# PWR_DC_IN.net
KiCad netlist of a schematic drawn in Altium Designer
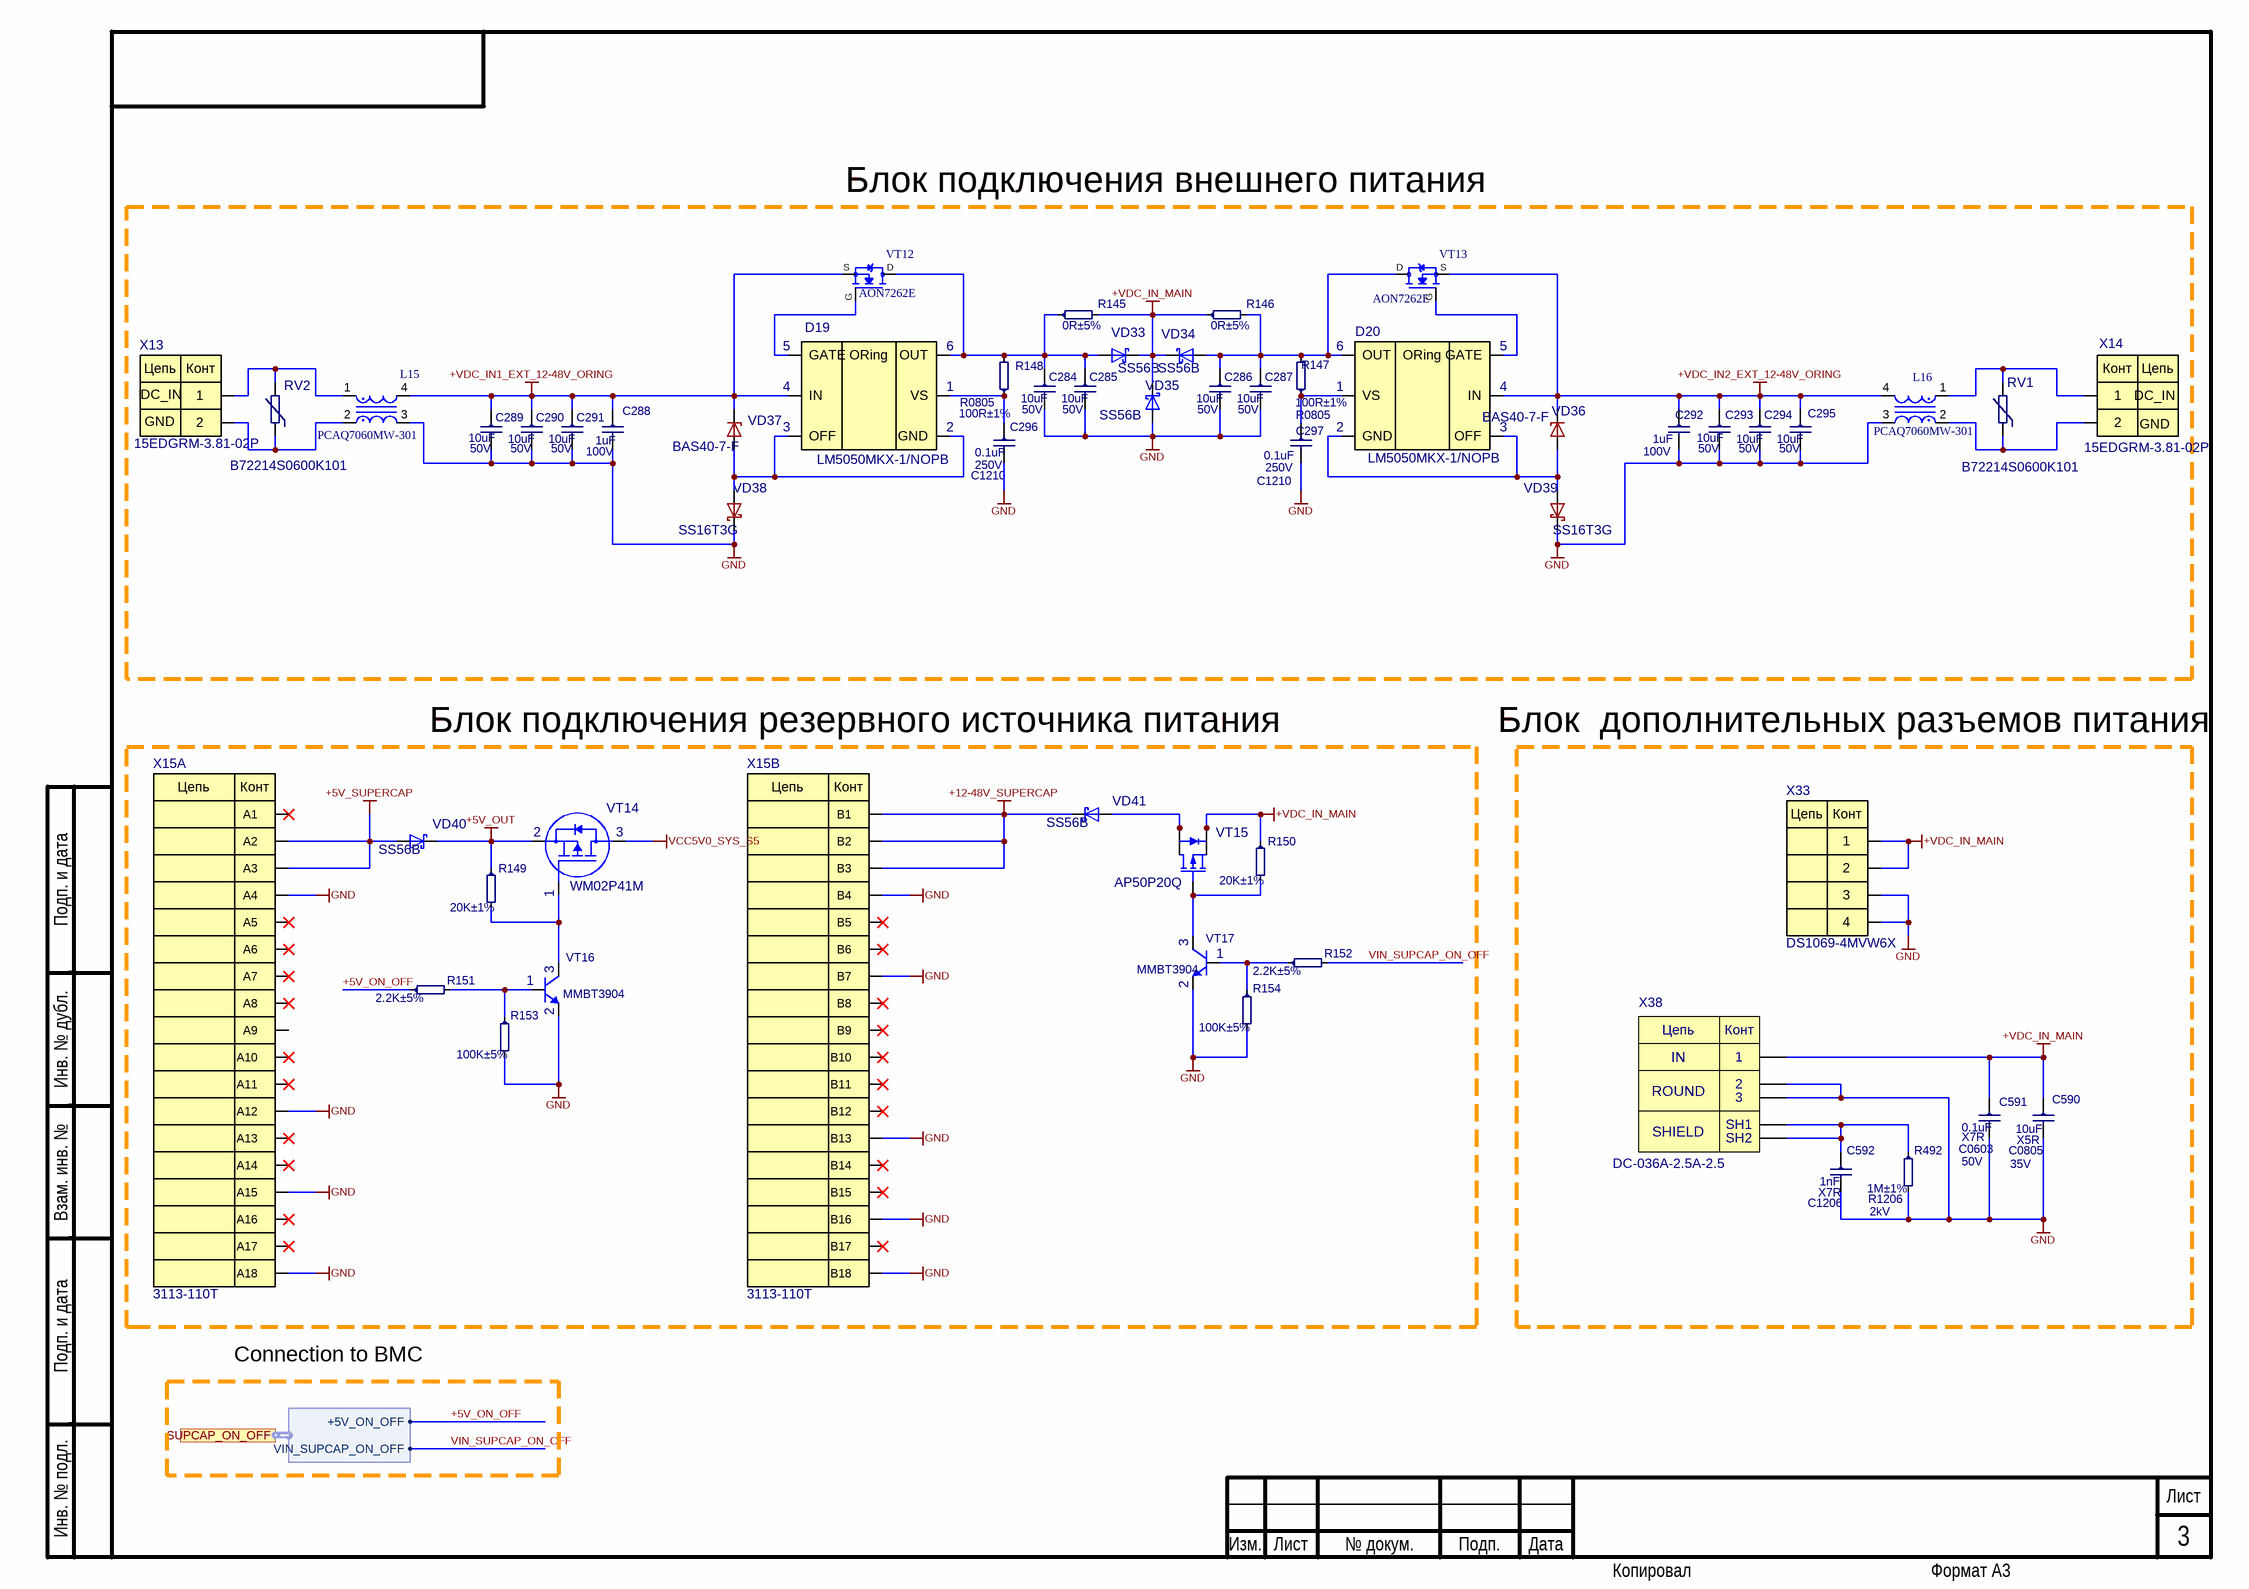
[diagram p0: PWR_DC_IN.SchDoc]

(export (version "E")
  (design (tool "Eeschema 10.0.6"))
  (components
    (comp (ref "C284")
      (value "10uF")
      (footprint "C1206")
      (fields
        (field (name "VOLTAGE") "50V")
        (field (name "PART NUMBER") "1206-X5R-50V-010uF±10%")
        (field (name "TOLERANCE") "10%")
        (field (name "MANUFACTURER") "Yageo")
      )
      (libsource (lib "ATB") (part "C"))
    )
    (comp (ref "C285")
      (value "10uF")
      (footprint "C1206")
      (fields
        (field (name "VOLTAGE") "50V")
        (field (name "PART NUMBER") "1206-X5R-50V-010uF±10%")
        (field (name "TOLERANCE") "10%")
        (field (name "MANUFACTURER") "Yageo")
      )
      (libsource (lib "ATB") (part "C"))
    )
    (comp (ref "C286")
      (value "10uF")
      (footprint "C1206")
      (fields
        (field (name "VOLTAGE") "50V")
        (field (name "PART NUMBER") "1206-X5R-50V-010uF±10%")
        (field (name "TOLERANCE") "10%")
        (field (name "MANUFACTURER") "Yageo")
      )
      (libsource (lib "ATB") (part "C"))
    )
    (comp (ref "C287")
      (value "10uF")
      (footprint "C1206")
      (fields
        (field (name "VOLTAGE") "50V")
        (field (name "PART NUMBER") "1206-X5R-50V-010uF±10%")
        (field (name "TOLERANCE") "10%")
        (field (name "MANUFACTURER") "Yageo")
      )
      (libsource (lib "ATB") (part "C"))
    )
    (comp (ref "C288")
      (value "1uF")
      (footprint "C1206")
      (fields
        (field (name "VOLTAGE") "100V")
        (field (name "PART NUMBER") "1206-X7R-100V-1uF±10%")
        (field (name "TOLERANCE") "10%")
        (field (name "MANUFACTURER") "CCTC")
      )
      (libsource (lib "ATB") (part "C"))
    )
    (comp (ref "C289")
      (value "10uF")
      (footprint "C1206")
      (fields
        (field (name "VOLTAGE") "50V")
        (field (name "PART NUMBER") "1206-X5R-50V-010uF±10%")
        (field (name "TOLERANCE") "10%")
        (field (name "MANUFACTURER") "Yageo")
      )
      (libsource (lib "ATB") (part "C"))
    )
    (comp (ref "C290")
      (value "10uF")
      (footprint "C1206")
      (fields
        (field (name "VOLTAGE") "50V")
        (field (name "PART NUMBER") "1206-X5R-50V-010uF±10%")
        (field (name "TOLERANCE") "10%")
        (field (name "MANUFACTURER") "Yageo")
      )
      (libsource (lib "ATB") (part "C"))
    )
    (comp (ref "C291")
      (value "10uF")
      (footprint "C1206")
      (fields
        (field (name "VOLTAGE") "50V")
        (field (name "PART NUMBER") "1206-X5R-50V-010uF±10%")
        (field (name "TOLERANCE") "10%")
        (field (name "MANUFACTURER") "Yageo")
      )
      (libsource (lib "ATB") (part "C"))
    )
    (comp (ref "C292")
      (value "1uF")
      (footprint "C1206")
      (fields
        (field (name "VOLTAGE") "100V")
        (field (name "PART NUMBER") "1206-X7R-100V-1uF±10%")
        (field (name "TOLERANCE") "10%")
        (field (name "MANUFACTURER") "CCTC")
      )
      (libsource (lib "ATB") (part "C"))
    )
    (comp (ref "C293")
      (value "10uF")
      (footprint "C1206")
      (fields
        (field (name "VOLTAGE") "50V")
        (field (name "PART NUMBER") "1206-X5R-50V-010uF±10%")
        (field (name "TOLERANCE") "10%")
        (field (name "MANUFACTURER") "Yageo")
      )
      (libsource (lib "ATB") (part "C"))
    )
    (comp (ref "C294")
      (value "10uF")
      (footprint "C1206")
      (fields
        (field (name "VOLTAGE") "50V")
        (field (name "PART NUMBER") "1206-X5R-50V-010uF±10%")
        (field (name "TOLERANCE") "10%")
        (field (name "MANUFACTURER") "Yageo")
      )
      (libsource (lib "ATB") (part "C"))
    )
    (comp (ref "C295")
      (value "10uF")
      (footprint "C1206")
      (fields
        (field (name "VOLTAGE") "50V")
        (field (name "PART NUMBER") "1206-X5R-50V-010uF±10%")
        (field (name "TOLERANCE") "10%")
        (field (name "MANUFACTURER") "Yageo")
      )
      (libsource (lib "ATB") (part "C"))
    )
    (comp (ref "C296")
      (value "0.1uF")
      (footprint "C1210")
      (fields
        (field (name "VOLTAGE") "250V")
        (field (name "CASE") "C1210")
        (field (name "PART NUMBER") "1210-X7R-250V-0.1uF±10%")
        (field (name "TOLERANCE") "10%")
        (field (name "MANUFACTURER") "Yageo")
      )
      (libsource (lib "ATB") (part "C"))
    )
    (comp (ref "C297")
      (value "0.1uF")
      (footprint "C1210")
      (fields
        (field (name "VOLTAGE") "250V")
        (field (name "CASE") "C1210")
        (field (name "PART NUMBER") "1210-X7R-250V-0.1uF±10%")
        (field (name "TOLERANCE") "10%")
        (field (name "MANUFACTURER") "Yageo")
      )
      (libsource (lib "ATB") (part "C"))
    )
    (comp (ref "C590")
      (value "10uF")
      (footprint "C0805")
      (fields
        (field (name "DIELECTRIC") "X5R")
        (field (name "VOLTAGE") "35V")
        (field (name "CASE") "C0805")
        (field (name "PART NUMBER") "0805-X5R-35V-10uF±10%")
        (field (name "TOLERANCE") "10%")
        (field (name "MANUFACTURER") "TDK Corporation")
      )
      (libsource (lib "ATB") (part "C"))
    )
    (comp (ref "C591")
      (value "0.1uF")
      (footprint "C0603")
      (fields
        (field (name "DIELECTRIC") "X7R")
        (field (name "VOLTAGE") "50V")
        (field (name "CASE") "C0603")
        (field (name "PART NUMBER") "0603-X7R-50V-0.1uF±10%")
        (field (name "TOLERANCE") "10%")
        (field (name "MANUFACTURER") "Yageo")
      )
      (libsource (lib "ATB") (part "C"))
    )
    (comp (ref "C592")
      (value "1nF")
      (footprint "C1206")
      (description "Ceramic Capacitor 1206 1nF ±10% 2kV X7R")
      (fields
        (field (name "DIELECTRIC") "X7R")
        (field (name "VOLTAGE") "2kV")
        (field (name "CASE") "C1206")
        (field (name "PART NUMBER") "1206-X7R-2K-1000pF±10%")
        (field (name "TOLERANCE") "10%")
      )
      (libsource (lib "ATB") (part "C"))
    )
    (comp (ref "D19")
      (value "LM5050MKX-1/NOPB")
      (footprint "LM5050MKX-1/NOPB")
      (description "High-Side OR-ing FET Controller")
      (fields (field (name "MANUFACTURER") "TI"))
      (libsource (lib "") (part "LM5050MKX-1/NOPB_1"))
    )
    (comp (ref "D20")
      (value "LM5050MKX-1/NOPB")
      (footprint "LM5050MKX-1/NOPB")
      (description "High-Side OR-ing FET Controller")
      (fields (field (name "MANUFACTURER") "TI"))
      (libsource (lib "LIB_RK") (part "LM5050MKX-1/NOPB"))
    )
    (comp (ref "L15")
      (value "PCAQ7060MW-301")
      (footprint "PCAQ7060MW-301")
      (description "300Ω@100MHz 10mΩ 2 SMD,7x6x3.8mm")
      (fields (field (name "MF") "Panasonic Electronic") (field (name "MP") "EEH-ZA1V151P"))
      (libsource (lib "") (part "PCAQ7060MW-301_1"))
    )
    (comp (ref "L16")
      (value "PCAQ7060MW-301")
      (footprint "PCAQ7060MW-301")
      (description "300Ω@100MHz 10mΩ 2 SMD,7x6x3.8mm")
      (fields (field (name "MF") "Panasonic Electronic") (field (name "MP") "EEH-ZA1V151P"))
      (libsource (lib "LIB_RK") (part "PCAQ7060MW-301"))
    )
    (comp (ref "R145")
      (value "0R±5%")
      (footprint "R2010")
      (description "Chip Resistor 2010 0Ω ±5% 200V ±200ppm/℃ Thick Film")
      (fields (field (name "PART NUMBER") "2010-0.75W-0R-200ppm±5%") (field (name "TOLERANCE") "5%"))
      (libsource (lib "ATB") (part "R"))
    )
    (comp (ref "R146")
      (value "0R±5%")
      (footprint "R2010")
      (description "Chip Resistor 2010 0Ω ±5% 200V ±200ppm/℃ Thick Film")
      (fields (field (name "PART NUMBER") "2010-0.75W-0R-200ppm±5%") (field (name "TOLERANCE") "5%"))
      (libsource (lib "ATB") (part "R"))
    )
    (comp (ref "R147")
      (value "100R±1%")
      (footprint "R0805")
      (fields
        (field (name "CASE") "R0805")
        (field (name "PART NUMBER") "0805-0.125W-100R-100ppm±1%")
        (field (name "TOLERANCE") "1%")
        (field (name "MANUFACTURER") "Yageo")
      )
      (libsource (lib "ATB") (part "R"))
    )
    (comp (ref "R148")
      (value "100R±1%")
      (footprint "R0805")
      (fields
        (field (name "CASE") "R0805")
        (field (name "PART NUMBER") "0805-0.125W-100R-100ppm±1%")
        (field (name "TOLERANCE") "1%")
        (field (name "MANUFACTURER") "Yageo")
      )
      (libsource (lib "ATB") (part "R"))
    )
    (comp (ref "R149")
      (value "20K±1%")
      (footprint "R0402")
      (description "Chip Resistor 0402 20kΩ ±1% 50V ±100ppm/℃ Thick Film")
      (fields (field (name "PART NUMBER") "0402-0.0625W-20K-100ppm±1%") (field (name "TOLERANCE") "1%"))
      (libsource (lib "ATB") (part "R"))
    )
    (comp (ref "R150")
      (value "20K±1%")
      (footprint "R0402")
      (description "Chip Resistor 0402 20kΩ ±1% 50V ±100ppm/℃ Thick Film")
      (fields (field (name "PART NUMBER") "0402-0.0625W-20K-100ppm±1%") (field (name "TOLERANCE") "1%"))
      (libsource (lib "ATB") (part "R"))
    )
    (comp (ref "R151")
      (value "2.2K±5%")
      (footprint "R0402")
      (fields
        (field (name "PART NUMBER") "0402-0.0625W-2.2K-100ppm±5%")
        (field (name "TOLERANCE") "5%")
        (field (name "MANUFACTURER") "Yageo")
      )
      (libsource (lib "ATB") (part "R"))
    )
    (comp (ref "R152")
      (value "2.2K±5%")
      (footprint "R0402")
      (fields
        (field (name "PART NUMBER") "0402-0.0625W-2.2K-100ppm±5%")
        (field (name "TOLERANCE") "5%")
        (field (name "MANUFACTURER") "Yageo")
      )
      (libsource (lib "ATB") (part "R"))
    )
    (comp (ref "R153")
      (value "100K±5%")
      (footprint "R0402")
      (fields
        (field (name "PART NUMBER") "0402-0.0625W-100K-100ppm±5%")
        (field (name "TOLERANCE") "5%")
        (field (name "MANUFACTURER") "Yageo")
      )
      (libsource (lib "ATB") (part "R"))
    )
    (comp (ref "R154")
      (value "100K±5%")
      (footprint "R0402")
      (fields
        (field (name "PART NUMBER") "0402-0.0625W-100K-100ppm±5%")
        (field (name "TOLERANCE") "5%")
        (field (name "MANUFACTURER") "Yageo")
      )
      (libsource (lib "ATB") (part "R"))
    )
    (comp (ref "R492")
      (value "1M±1%")
      (footprint "R1206")
      (description "Chip Resistor 1206 1MΩ ±1% 200V ±100ppm/℃ Thick Film")
      (fields
        (field (name "CASE") "R1206")
        (field (name "PART NUMBER") "1206-0.25W-1M-100ppm±1%")
        (field (name "TOLERANCE") "1%")
      )
      (libsource (lib "ATB") (part "R"))
    )
    (comp (ref "RV1")
      (value "B72214S0600K101")
      (footprint "Var_dia15.5")
      (description "Varistor")
      (fields (field (name "VOLTAGE") "320V") (field (name "MANUFACTURER") "Epcos"))
      (libsource (lib "ATB") (part "RV"))
    )
    (comp (ref "RV2")
      (value "B72214S0600K101")
      (footprint "Var_dia15.5")
      (description "Varistor")
      (fields (field (name "VOLTAGE") "320V") (field (name "MANUFACTURER") "Epcos"))
      (libsource (lib "ATB") (part "RV"))
    )
    (comp (ref "VD33")
      (value "SS56B")
      (footprint "DO-214AA")
      (description "Schottky Rectifier")
      (fields (field (name "MANUFACTURER") "Yangjie (YJ)"))
      (libsource (lib "ATB") (part "Shotki"))
    )
    (comp (ref "VD34")
      (value "SS56B")
      (footprint "DO-214AA")
      (description "Schottky Rectifier")
      (fields (field (name "MANUFACTURER") "Yangjie (YJ)"))
      (libsource (lib "ATB") (part "Shotki"))
    )
    (comp (ref "VD35")
      (value "SS56B")
      (footprint "DO-214AA")
      (description "Schottky Rectifier")
      (fields (field (name "MANUFACTURER") "Yangjie (YJ)"))
      (libsource (lib "ATB") (part "Shotki"))
    )
    (comp (ref "VD36")
      (value "BAS40-7-F")
      (footprint "SOT23")
      (description "600mA 1 Independent 40V 1V@40mA 200mA SOT-23 Single Diodes RoHS")
      (fields (field (name "MANUFACTURER") "Diodes Incorporated"))
      (libsource (lib "ATB") (part "LM4040"))
    )
    (comp (ref "VD37")
      (value "BAS40-7-F")
      (footprint "SOT23")
      (description "600mA 1 Independent 40V 1V@40mA 200mA SOT-23 Single Diodes RoHS")
      (fields (field (name "MANUFACTURER") "Diodes Incorporated"))
      (libsource (lib "ATB") (part "LM4040"))
    )
    (comp (ref "VD38")
      (value "SS16T3G")
      (footprint "DO-214AC")
      (description "Schottky Power Rectifier")
      (fields (field (name "MANUFACTURER") "ON Semiconductor"))
      (libsource (lib "") (part "Shotki_1"))
    )
    (comp (ref "VD39")
      (value "SS16T3G")
      (footprint "DO-214AC")
      (description "Schottky Power Rectifier")
      (fields (field (name "MANUFACTURER") "ON Semiconductor"))
      (libsource (lib "") (part "Shotki_1"))
    )
    (comp (ref "VD40")
      (value "SS56B")
      (footprint "DO-214AA")
      (description "Schottky Rectifier")
      (fields (field (name "MANUFACTURER") "Yangjie (YJ)"))
      (libsource (lib "ATB") (part "Shotki"))
    )
    (comp (ref "VD41")
      (value "SS56B")
      (footprint "DO-214AA")
      (description "Schottky Rectifier")
      (fields (field (name "MANUFACTURER") "Yangjie (YJ)"))
      (libsource (lib "ATB") (part "Shotki"))
    )
    (comp (ref "VT12")
      (value "AON7262E")
      (footprint "AON7262E")
      (description "60V 6.2mΩ@10V,20A 2.2V@250uA N Channel DFN-8(3.3x3.3) MOSFET")
      (fields (field (name "MANUFACTURER") "Alpha & Omega"))
      (libsource (lib "LIB_RK") (part "AON7262E"))
    )
    (comp (ref "VT13")
      (value "AON7262E")
      (footprint "AON7262E")
      (description "60V 6.2mΩ@10V,20A 2.2V@250uA N Channel DFN-8(3.3x3.3) MOSFET")
      (fields (field (name "MANUFACTURER") "Alpha & Omega"))
      (libsource (lib "LIB_RK") (part "AON7262E"))
    )
    (comp (ref "VT14")
      (value "WM02P41M")
      (footprint "SOT23")
      (description "Small signal mosfet")
      (fields (field (name "VOLTAGE") "-20V") (field (name "MANUFACTURER") "Wayon"))
      (libsource (lib "ATB") (part "WM02P41M"))
    )
    (comp (ref "VT15")
      (value "AP50P20Q")
      (footprint "AP50P20Q")
      (description "20V 50A 40W 6.6mΩ@4.5V,15A 650mV@250uA P Channel WDFN-8(3x3) MOSFETs")
      (fields (field (name "MANUFACTURER") "ALLPOWER"))
      (libsource (lib "LIB_RK") (part "AP50P20Q"))
    )
    (comp (ref "VT16")
      (value "MMBT3904")
      (footprint "SOT23")
      (description "NPN transistor")
      (fields (field (name "VOLTAGE") "40V") (field (name "MANUFACTURER") "Diotec Semiconductor"))
      (libsource (lib "ATB") (part "BC846BLT1G"))
    )
    (comp (ref "VT17")
      (value "MMBT3904")
      (footprint "SOT23")
      (description "NPN transistor")
      (fields (field (name "VOLTAGE") "40V") (field (name "MANUFACTURER") "Diotec Semiconductor"))
      (libsource (lib "ATB") (part "BC846BLT1G"))
    )
    (comp (ref "X13")
      (value "15EDGRM-3.81-02P")
      (footprint "15EDGRM-3.81-02P")
      (description "Разъемный клеммный блок на плату, 2 контакта. Серия 15EDGRM-3.81")
      (fields (field (name "MANUFACTURER") "DEGSON"))
      (libsource (lib "") (part "15EDGRM-3.81-02P_1"))
    )
    (comp (ref "X14")
      (value "15EDGRM-3.81-02P")
      (footprint "15EDGRM-3.81-02P")
      (description "Разъемный клеммный блок на плату, 2 контакта. Серия 15EDGRM-3.81")
      (fields (field (name "MANUFACTURER") "DEGSON"))
      (libsource (lib "LIB_RK") (part "15EDGRM-3.81-02P"))
    )
    (comp (ref "X15")
      (value "3113-110T")
      (footprint "3113-110T")
      (description "PCI Connector, Vertical, Surface Mount, x1, 36 Positions, 1.00mm (0.039in) Pitch")
      (fields (field (name "MANUFACTURER") "UMAX"))
      (libsource (lib "LIB_RK") (part "3113-110T"))
    )
    (comp (ref "X33")
      (value "DS1069-4MVW6X")
      (footprint "DS1069-4MVW6X")
      (description "1 XH 4P -25℃~+85℃ 2.5mm 3A 250V 1x4P Through Hole,P=2.5mm Headers, Male Pins RoHS")
      (fields (field (name "MANUFACTURER") "CONNFLY"))
      (libsource (lib "LIB_RK") (part "DS1069-4MVW6X"))
    )
    (comp (ref "X38")
      (value "DC-036A-2.5A-2.5")
      (footprint "DC-036A-2.5A-2.5")
      (description "DC Power Connector Bend-in, -20℃~+70℃, 2.5mm 6mm, 2.5A 24V")
      (fields (field (name "MANUFACTURER") "XKB Connection"))
      (libsource (lib "ATB") (part "DC-036A-2.5A-2.5"))
    )
  )
  (nets
    (net (code "2") (name "+5V_OUT") (class "Default")
      (node (ref "R149") (pin "1") (pinfunction "1_1") (pintype "passive"))
      (node (ref "VD40") (pin "1") (pinfunction "K_1") (pintype "passive"))
      (node (ref "VT14") (pin "2") (pinfunction "2_2") (pintype "passive"))
    )
    (net (code "3") (name "+5V_SUPERCAP") (class "Default")
      (node (ref "VD40") (pin "2") (pinfunction "A_2") (pintype "passive"))
      (node (ref "X15") (pin "A2") (pinfunction "A2_A2") (pintype "passive"))
      (node (ref "X15") (pin "A3") (pinfunction "A3_A3") (pintype "passive"))
    )
    (net (code "4") (name "+12-48V_SUPERCAP") (class "Default")
      (node (ref "VD41") (pin "1") (pinfunction "K_1") (pintype "passive"))
      (node (ref "X15") (pin "B1") (pinfunction "B1_B1") (pintype "passive"))
      (node (ref "X15") (pin "B2") (pinfunction "B2_B2") (pintype "passive"))
      (node (ref "X15") (pin "B3") (pinfunction "B3_B3") (pintype "passive"))
    )
    (net (code "5") (name "+VDC_IN1_EXT_12-48V_ORING") (class "Default")
      (node (ref "C288") (pin "1") (pinfunction "1_1") (pintype "passive"))
      (node (ref "C289") (pin "1") (pinfunction "1_1") (pintype "passive"))
      (node (ref "C290") (pin "1") (pinfunction "1_1") (pintype "passive"))
      (node (ref "C291") (pin "1") (pinfunction "1_1") (pintype "passive"))
      (node (ref "D19") (pin "4") (pinfunction "IN_4") (pintype "passive"))
      (node (ref "L15") (pin "4") (pinfunction "4_4") (pintype "passive"))
      (node (ref "VD37") (pin "1") (pinfunction "C_1") (pintype "passive"))
      (node (ref "VT12") (pin "S") (pinfunction "S_S") (pintype "passive"))
    )
    (net (code "6") (name "+VDC_IN2_EXT_12-48V_ORING") (class "Default")
      (node (ref "C292") (pin "1") (pinfunction "1_1") (pintype "passive"))
      (node (ref "C293") (pin "1") (pinfunction "1_1") (pintype "passive"))
      (node (ref "C294") (pin "1") (pinfunction "1_1") (pintype "passive"))
      (node (ref "C295") (pin "1") (pinfunction "1_1") (pintype "passive"))
      (node (ref "D20") (pin "4") (pinfunction "IN_4") (pintype "passive"))
      (node (ref "L16") (pin "4") (pinfunction "4_4") (pintype "passive"))
      (node (ref "VD36") (pin "1") (pinfunction "C_1") (pintype "passive"))
      (node (ref "VT13") (pin "S") (pinfunction "S_S") (pintype "passive"))
    )
    (net (code "7") (name "+VDC_IN_MAIN") (class "Default")
      (node (ref "C590") (pin "1") (pinfunction "1_1") (pintype "passive"))
      (node (ref "C591") (pin "1") (pinfunction "1_1") (pintype "passive"))
      (node (ref "R145") (pin "2") (pinfunction "2_2") (pintype "passive"))
      (node (ref "R146") (pin "1") (pinfunction "1_1") (pintype "passive"))
      (node (ref "R150") (pin "1") (pinfunction "1_1") (pintype "passive"))
      (node (ref "VD33") (pin "1") (pinfunction "K_1") (pintype "passive"))
      (node (ref "VD34") (pin "1") (pinfunction "K_1") (pintype "passive"))
      (node (ref "VD35") (pin "1") (pinfunction "K_1") (pintype "passive"))
      (node (ref "VT15") (pin "1") (pinfunction "1_1") (pintype "passive"))
      (node (ref "VT15") (pin "2") (pinfunction "2_2") (pintype "passive"))
      (node (ref "VT15") (pin "3") (pinfunction "3_3") (pintype "passive"))
      (node (ref "X33") (pin "1") (pinfunction "1_1") (pintype "passive"))
      (node (ref "X33") (pin "2") (pinfunction "2_2") (pintype "passive"))
      (node (ref "X38") (pin "1") (pinfunction "IN_1") (pintype "passive"))
    )
    (net (code "8") (name "/+5V_ON_OFF") (class "Default")
      (node (ref "R151") (pin "1") (pinfunction "1_1") (pintype "passive"))
    )
    (net (code "9") (name "/VIN_SUPCAP_ON_OFF") (class "Default")
      (node (ref "R152") (pin "2") (pinfunction "2_2") (pintype "passive"))
    )
    (net (code "11") (name "GND") (class "Default")
      (node (ref "C284") (pin "2") (pinfunction "2_2") (pintype "passive"))
      (node (ref "C285") (pin "2") (pinfunction "2_2") (pintype "passive"))
      (node (ref "C286") (pin "2") (pinfunction "2_2") (pintype "passive"))
      (node (ref "C287") (pin "2") (pinfunction "2_2") (pintype "passive"))
      (node (ref "C288") (pin "2") (pinfunction "2_2") (pintype "passive"))
      (node (ref "C289") (pin "2") (pinfunction "2_2") (pintype "passive"))
      (node (ref "C290") (pin "2") (pinfunction "2_2") (pintype "passive"))
      (node (ref "C291") (pin "2") (pinfunction "2_2") (pintype "passive"))
      (node (ref "C292") (pin "2") (pinfunction "2_2") (pintype "passive"))
      (node (ref "C293") (pin "2") (pinfunction "2_2") (pintype "passive"))
      (node (ref "C294") (pin "2") (pinfunction "2_2") (pintype "passive"))
      (node (ref "C295") (pin "2") (pinfunction "2_2") (pintype "passive"))
      (node (ref "C296") (pin "2") (pinfunction "2_2") (pintype "passive"))
      (node (ref "C297") (pin "2") (pinfunction "2_2") (pintype "passive"))
      (node (ref "C590") (pin "2") (pinfunction "2_2") (pintype "passive"))
      (node (ref "C591") (pin "2") (pinfunction "2_2") (pintype "passive"))
      (node (ref "C592") (pin "2") (pinfunction "2_2") (pintype "passive"))
      (node (ref "L15") (pin "3") (pinfunction "3_3") (pintype "passive"))
      (node (ref "L16") (pin "3") (pinfunction "3_3") (pintype "passive"))
      (node (ref "R153") (pin "2") (pinfunction "2_2") (pintype "passive"))
      (node (ref "R154") (pin "2") (pinfunction "2_2") (pintype "passive"))
      (node (ref "R492") (pin "2") (pinfunction "2_2") (pintype "passive"))
      (node (ref "VD35") (pin "2") (pinfunction "A_2") (pintype "passive"))
      (node (ref "VD38") (pin "1") (pinfunction "C_1") (pintype "passive"))
      (node (ref "VD39") (pin "1") (pinfunction "C_1") (pintype "passive"))
      (node (ref "VT16") (pin "2") (pinfunction "E_2") (pintype "passive"))
      (node (ref "VT17") (pin "2") (pinfunction "E_2") (pintype "passive"))
      (node (ref "X15") (pin "A12") (pinfunction "A12_A12") (pintype "passive"))
      (node (ref "X15") (pin "A15") (pinfunction "A15_A15") (pintype "passive"))
      (node (ref "X15") (pin "A18") (pinfunction "A18_A18") (pintype "passive"))
      (node (ref "X15") (pin "A4") (pinfunction "A4_A4") (pintype "passive"))
      (node (ref "X15") (pin "B13") (pinfunction "B13_B13") (pintype "passive"))
      (node (ref "X15") (pin "B16") (pinfunction "B16_B16") (pintype "passive"))
      (node (ref "X15") (pin "B18") (pinfunction "B18_B18") (pintype "passive"))
      (node (ref "X15") (pin "B4") (pinfunction "B4_B4") (pintype "passive"))
      (node (ref "X15") (pin "B7") (pinfunction "B7_B7") (pintype "passive"))
      (node (ref "X33") (pin "3") (pinfunction "3_3") (pintype "passive"))
      (node (ref "X33") (pin "4") (pinfunction "4_4") (pintype "passive"))
      (node (ref "X38") (pin "2") (pinfunction "ROUND_2") (pintype "passive"))
      (node (ref "X38") (pin "3") (pinfunction "ROUND_3") (pintype "passive"))
    )
    (net (code "12") (name "Net-(C592-Pad1)") (class "Default")
      (node (ref "C592") (pin "1") (pinfunction "1_1") (pintype "passive"))
      (node (ref "R492") (pin "1") (pinfunction "1_1") (pintype "passive"))
      (node (ref "X38") (pin "SH1") (pinfunction "SH1_SH1") (pintype "passive"))
      (node (ref "X38") (pin "SH2") (pinfunction "SH2_SH2") (pintype "passive"))
    )
    (net (code "13") (name "Net-(D19-GATE)") (class "Default")
      (node (ref "D19") (pin "5") (pinfunction "GATE_5") (pintype "passive"))
      (node (ref "VT12") (pin "G") (pinfunction "G_G") (pintype "passive"))
    )
    (net (code "14") (name "Net-(D19-GND)") (class "Default")
      (node (ref "D19") (pin "2") (pinfunction "GND_2") (pintype "passive"))
      (node (ref "D19") (pin "3") (pinfunction "OFF_3") (pintype "passive"))
      (node (ref "VD37") (pin "2") (pinfunction "A_2") (pintype "passive"))
      (node (ref "VD38") (pin "2") (pinfunction "A_2") (pintype "passive"))
    )
    (net (code "15") (name "Net-(D19-OUT)") (class "Default")
      (node (ref "C284") (pin "1") (pinfunction "1_1") (pintype "passive"))
      (node (ref "C285") (pin "1") (pinfunction "1_1") (pintype "passive"))
      (node (ref "D19") (pin "6") (pinfunction "OUT_6") (pintype "passive"))
      (node (ref "R145") (pin "1") (pinfunction "1_1") (pintype "passive"))
      (node (ref "R148") (pin "2") (pinfunction "2_2") (pintype "passive"))
      (node (ref "VD33") (pin "2") (pinfunction "A_2") (pintype "passive"))
      (node (ref "VT12") (pin "D") (pinfunction "D_D") (pintype "passive"))
    )
    (net (code "16") (name "Net-(D19-VS)") (class "Default")
      (node (ref "C296") (pin "1") (pinfunction "1_1") (pintype "passive"))
      (node (ref "D19") (pin "1") (pinfunction "VS_1") (pintype "passive"))
      (node (ref "R148") (pin "1") (pinfunction "1_1") (pintype "passive"))
    )
    (net (code "17") (name "Net-(D20-GATE)") (class "Default")
      (node (ref "D20") (pin "5") (pinfunction "GATE_5") (pintype "passive"))
      (node (ref "VT13") (pin "G") (pinfunction "G_G") (pintype "passive"))
    )
    (net (code "18") (name "Net-(D20-GND)") (class "Default")
      (node (ref "D20") (pin "2") (pinfunction "GND_2") (pintype "passive"))
      (node (ref "D20") (pin "3") (pinfunction "OFF_3") (pintype "passive"))
      (node (ref "VD36") (pin "2") (pinfunction "A_2") (pintype "passive"))
      (node (ref "VD39") (pin "2") (pinfunction "A_2") (pintype "passive"))
    )
    (net (code "19") (name "Net-(D20-OUT)") (class "Default")
      (node (ref "C286") (pin "1") (pinfunction "1_1") (pintype "passive"))
      (node (ref "C287") (pin "1") (pinfunction "1_1") (pintype "passive"))
      (node (ref "D20") (pin "6") (pinfunction "OUT_6") (pintype "passive"))
      (node (ref "R146") (pin "2") (pinfunction "2_2") (pintype "passive"))
      (node (ref "R147") (pin "2") (pinfunction "2_2") (pintype "passive"))
      (node (ref "VD34") (pin "2") (pinfunction "A_2") (pintype "passive"))
      (node (ref "VT13") (pin "D") (pinfunction "D_D") (pintype "passive"))
    )
    (net (code "20") (name "Net-(D20-VS)") (class "Default")
      (node (ref "C297") (pin "1") (pinfunction "1_1") (pintype "passive"))
      (node (ref "D20") (pin "1") (pinfunction "VS_1") (pintype "passive"))
      (node (ref "R147") (pin "1") (pinfunction "1_1") (pintype "passive"))
    )
    (net (code "21") (name "Net-(L15-Pad1)") (class "Default")
      (node (ref "L15") (pin "1") (pinfunction "1_1") (pintype "passive"))
      (node (ref "RV2") (pin "2") (pinfunction "2_2") (pintype "passive"))
      (node (ref "X13") (pin "1") (pinfunction "1_1") (pintype "passive"))
    )
    (net (code "22") (name "Net-(L15-Pad2)") (class "Default")
      (node (ref "L15") (pin "2") (pinfunction "2_2") (pintype "passive"))
      (node (ref "RV2") (pin "1") (pinfunction "1_1") (pintype "passive"))
      (node (ref "X13") (pin "2") (pinfunction "2_2") (pintype "passive"))
    )
    (net (code "23") (name "Net-(L16-Pad1)") (class "Default")
      (node (ref "L16") (pin "1") (pinfunction "1_1") (pintype "passive"))
      (node (ref "RV1") (pin "2") (pinfunction "2_2") (pintype "passive"))
      (node (ref "X14") (pin "1") (pinfunction "1_1") (pintype "passive"))
    )
    (net (code "24") (name "Net-(L16-Pad2)") (class "Default")
      (node (ref "L16") (pin "2") (pinfunction "2_2") (pintype "passive"))
      (node (ref "RV1") (pin "1") (pinfunction "1_1") (pintype "passive"))
      (node (ref "X14") (pin "2") (pinfunction "2_2") (pintype "passive"))
    )
    (net (code "25") (name "Net-(VD41-A)") (class "Default")
      (node (ref "VD41") (pin "2") (pinfunction "A_2") (pintype "passive"))
      (node (ref "VT15") (pin "5") (pinfunction "5_5") (pintype "passive"))
      (node (ref "VT15") (pin "6") (pinfunction "6_6") (pintype "passive"))
      (node (ref "VT15") (pin "7") (pinfunction "7_7") (pintype "passive"))
      (node (ref "VT15") (pin "8") (pinfunction "8_8") (pintype "passive"))
    )
    (net (code "26") (name "Net-(VT16-B)") (class "Default")
      (node (ref "R151") (pin "2") (pinfunction "2_2") (pintype "passive"))
      (node (ref "R153") (pin "1") (pinfunction "1_1") (pintype "passive"))
      (node (ref "VT16") (pin "1") (pinfunction "B_1") (pintype "passive"))
    )
    (net (code "27") (name "Net-(VT16-C)") (class "Default")
      (node (ref "R149") (pin "2") (pinfunction "2_2") (pintype "passive"))
      (node (ref "VT14") (pin "1") (pinfunction "1_1") (pintype "passive"))
      (node (ref "VT16") (pin "3") (pinfunction "C_3") (pintype "passive"))
    )
    (net (code "28") (name "Net-(VT17-B)") (class "Default")
      (node (ref "R152") (pin "1") (pinfunction "1_1") (pintype "passive"))
      (node (ref "R154") (pin "1") (pinfunction "1_1") (pintype "passive"))
      (node (ref "VT17") (pin "1") (pinfunction "B_1") (pintype "passive"))
    )
    (net (code "29") (name "Net-(VT17-C)") (class "Default")
      (node (ref "R150") (pin "2") (pinfunction "2_2") (pintype "passive"))
      (node (ref "VT15") (pin "4") (pinfunction "4_4") (pintype "passive"))
      (node (ref "VT17") (pin "3") (pinfunction "C_3") (pintype "passive"))
    )
    (net (code "30") (name "VCC5V0_SYS_S5") (class "Default")
      (node (ref "VT14") (pin "3") (pinfunction "3_3") (pintype "passive"))
    )
    (net (code "31") (name "unconnected-(X15-PadA1)") (class "Default")
      (node (ref "X15") (pin "A1") (pinfunction "A1_A1") (pintype "passive+no_connect"))
    )
    (net (code "32") (name "unconnected-(X15-PadA5)") (class "Default")
      (node (ref "X15") (pin "A5") (pinfunction "A5_A5") (pintype "passive+no_connect"))
    )
    (net (code "33") (name "unconnected-(X15-PadA6)") (class "Default")
      (node (ref "X15") (pin "A6") (pinfunction "A6_A6") (pintype "passive+no_connect"))
    )
    (net (code "34") (name "unconnected-(X15-PadA7)") (class "Default")
      (node (ref "X15") (pin "A7") (pinfunction "A7_A7") (pintype "passive+no_connect"))
    )
    (net (code "35") (name "unconnected-(X15-PadA8)") (class "Default")
      (node (ref "X15") (pin "A8") (pinfunction "A8_A8") (pintype "passive+no_connect"))
    )
    (net (code "36") (name "unconnected-(X15-PadA9)") (class "Default")
      (node (ref "X15") (pin "A9") (pinfunction "A9_A9") (pintype "passive"))
    )
    (net (code "37") (name "unconnected-(X15-PadA10)") (class "Default")
      (node (ref "X15") (pin "A10") (pinfunction "A10_A10") (pintype "passive+no_connect"))
    )
    (net (code "38") (name "unconnected-(X15-PadA11)") (class "Default")
      (node (ref "X15") (pin "A11") (pinfunction "A11_A11") (pintype "passive+no_connect"))
    )
    (net (code "39") (name "unconnected-(X15-PadA13)") (class "Default")
      (node (ref "X15") (pin "A13") (pinfunction "A13_A13") (pintype "passive+no_connect"))
    )
    (net (code "40") (name "unconnected-(X15-PadA14)") (class "Default")
      (node (ref "X15") (pin "A14") (pinfunction "A14_A14") (pintype "passive+no_connect"))
    )
    (net (code "41") (name "unconnected-(X15-PadA16)") (class "Default")
      (node (ref "X15") (pin "A16") (pinfunction "A16_A16") (pintype "passive+no_connect"))
    )
    (net (code "42") (name "unconnected-(X15-PadA17)") (class "Default")
      (node (ref "X15") (pin "A17") (pinfunction "A17_A17") (pintype "passive+no_connect"))
    )
    (net (code "43") (name "unconnected-(X15-PadB5)") (class "Default")
      (node (ref "X15") (pin "B5") (pinfunction "B5_B5") (pintype "passive+no_connect"))
    )
    (net (code "44") (name "unconnected-(X15-PadB6)") (class "Default")
      (node (ref "X15") (pin "B6") (pinfunction "B6_B6") (pintype "passive+no_connect"))
    )
    (net (code "45") (name "unconnected-(X15-PadB8)") (class "Default")
      (node (ref "X15") (pin "B8") (pinfunction "B8_B8") (pintype "passive+no_connect"))
    )
    (net (code "46") (name "unconnected-(X15-PadB9)") (class "Default")
      (node (ref "X15") (pin "B9") (pinfunction "B9_B9") (pintype "passive+no_connect"))
    )
    (net (code "47") (name "unconnected-(X15-PadB10)") (class "Default")
      (node (ref "X15") (pin "B10") (pinfunction "B10_B10") (pintype "passive+no_connect"))
    )
    (net (code "48") (name "unconnected-(X15-PadB11)") (class "Default")
      (node (ref "X15") (pin "B11") (pinfunction "B11_B11") (pintype "passive+no_connect"))
    )
    (net (code "49") (name "unconnected-(X15-PadB12)") (class "Default")
      (node (ref "X15") (pin "B12") (pinfunction "B12_B12") (pintype "passive+no_connect"))
    )
    (net (code "50") (name "unconnected-(X15-PadB14)") (class "Default")
      (node (ref "X15") (pin "B14") (pinfunction "B14_B14") (pintype "passive+no_connect"))
    )
    (net (code "51") (name "unconnected-(X15-PadB15)") (class "Default")
      (node (ref "X15") (pin "B15") (pinfunction "B15_B15") (pintype "passive+no_connect"))
    )
    (net (code "52") (name "unconnected-(X15-PadB17)") (class "Default")
      (node (ref "X15") (pin "B17") (pinfunction "B17_B17") (pintype "passive+no_connect"))
    )
  )
)
